# ultrasonic.net
KiCad netlist of a schematic drawn in Altium Designer
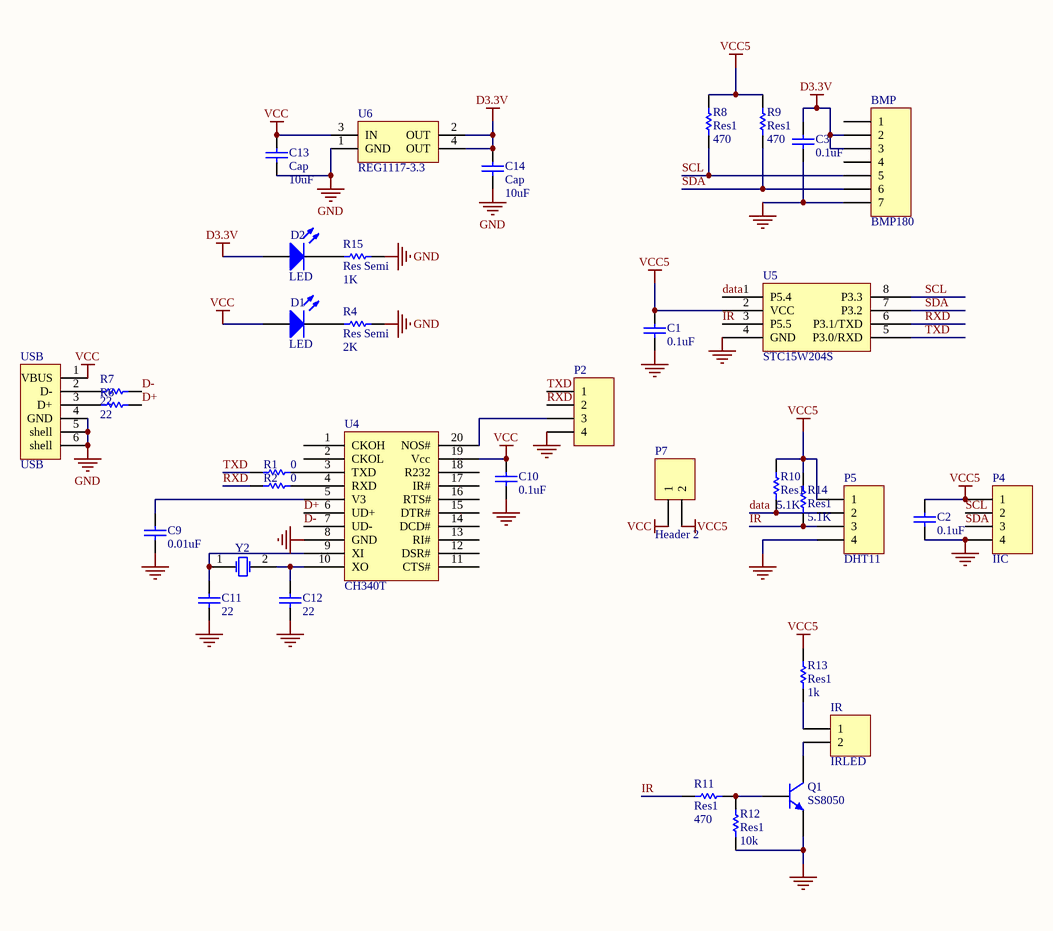
[diagram p0: ultrasonic.SCHDOC]

(export (version "E")
  (design (tool "Eeschema 10.0.6"))
  (components
    (comp (ref "BMP")
      (value "BMP180")
      (footprint "BMP180")
      (description "Header, 7-Pin")
      (fields (field (name "PUBLISHER") "Altium Limited"))
      (libsource (lib "Miscellaneous Connectors") (part "Header 7"))
    )
    (comp (ref "C1")
      (value "0.1uF")
      (footprint "C0603")
      (description "Capacitor")
      (fields (field (name "Comment") "Cap") (field (name "PUBLISHER") "Altium Limited"))
      (libsource (lib "Miscellaneous Devices") (part "Cap"))
    )
    (comp (ref "C2")
      (value "0.1uF")
      (footprint "C0603")
      (description "Capacitor")
      (fields (field (name "Comment") "Cap") (field (name "PUBLISHER") "Altium Limited"))
      (libsource (lib "Miscellaneous Devices") (part "Cap"))
    )
    (comp (ref "C3")
      (value "0.1uF")
      (footprint "C0603")
      (description "Capacitor")
      (fields (field (name "Comment") "Cap") (field (name "PUBLISHER") "Altium Limited"))
      (libsource (lib "Miscellaneous Devices") (part "Cap"))
    )
    (comp (ref "C9")
      (value "0.01uF")
      (footprint "C0603")
      (description "Capacitor")
      (fields (field (name "Comment") "Cap") (field (name "PUBLISHER") "Altium Limited"))
      (libsource (lib "Miscellaneous Devices") (part "Cap"))
    )
    (comp (ref "C10")
      (value "0.1uF")
      (footprint "C0603")
      (description "Capacitor")
      (fields (field (name "Comment") "Cap") (field (name "PUBLISHER") "Altium Limited"))
      (libsource (lib "Miscellaneous Devices") (part "Cap"))
    )
    (comp (ref "C11")
      (value "22")
      (footprint "C0603")
      (description "Capacitor")
      (fields (field (name "Comment") "Cap") (field (name "PUBLISHER") "Altium Limited"))
      (libsource (lib "Miscellaneous Devices") (part "Cap"))
    )
    (comp (ref "C12")
      (value "22")
      (footprint "C0603")
      (description "Capacitor")
      (fields (field (name "Comment") "Cap") (field (name "PUBLISHER") "Altium Limited"))
      (libsource (lib "Miscellaneous Devices") (part "Cap"))
    )
    (comp (ref "C13")
      (value "Cap")
      (footprint "CAP0805(2512)")
      (description "Capacitor")
      (fields (field (name "ALTIUM_VALUE") "10uF") (field (name "PUBLISHER") "Altium Limited"))
      (libsource (lib "Miscellaneous Devices") (part "Cap"))
    )
    (comp (ref "C14")
      (value "Cap")
      (footprint "RES0805(2012M)")
      (description "Capacitor")
      (fields (field (name "ALTIUM_VALUE") "10uF") (field (name "PUBLISHER") "Altium Limited"))
      (libsource (lib "Miscellaneous Devices") (part "Cap"))
    )
    (comp (ref "D1")
      (value "LED")
      (footprint "LED_0805")
      (description "Typical BLUE SiC LED")
      (fields (field (name "PUBLISHER") "Altium Limited"))
      (libsource (lib "Miscellaneous Devices") (part "LED3"))
    )
    (comp (ref "D2")
      (value "LED")
      (footprint "LED_0805")
      (description "Typical BLUE SiC LED")
      (fields (field (name "PUBLISHER") "Altium Limited"))
      (libsource (lib "Miscellaneous Devices") (part "LED3"))
    )
    (comp (ref "IR")
      (value "IRLED")
      (footprint "HDR1X2")
      (description "Header, 2-Pin")
      (fields (field (name "PUBLISHER") "Altium Limited"))
      (libsource (lib "") (part "Header 2_1"))
    )
    (comp (ref "P2")
      (value "Header 4")
      (footprint "HDR1X4")
      (description "Header, 4-Pin")
      (fields (field (name "PUBLISHER") "Altium Limited"))
      (libsource (lib "Miscellaneous Connectors") (part "Header 4"))
    )
    (comp (ref "P4")
      (value "IIC")
      (footprint "HDR1X4")
      (description "Header, 4-Pin")
      (fields (field (name "PUBLISHER") "Altium Limited"))
      (libsource (lib "Miscellaneous Connectors") (part "Header 4"))
    )
    (comp (ref "P5")
      (value "DHT11")
      (footprint "HDR1X4")
      (description "Header, 4-Pin")
      (fields (field (name "PUBLISHER") "Altium Limited"))
      (libsource (lib "Miscellaneous Connectors") (part "Header 4"))
    )
    (comp (ref "P7")
      (value "Header 2")
      (footprint "HDR1X2")
      (description "Header, 2-Pin")
      (fields (field (name "PUBLISHER") "Altium Limited"))
      (libsource (lib "Miscellaneous Connectors") (part "Header 2"))
    )
    (comp (ref "Q1")
      (value "SS8050")
      (footprint "SOT95P240-3N")
      (description "NPN Bipolar Transistor")
      (fields (field (name "PUBLISHER") "Altium Limited"))
      (libsource (lib "Miscellaneous Devices") (part "NPN"))
    )
    (comp (ref "R1")
      (value "0")
      (footprint "C0603")
      (description "Semiconductor Resistor")
      (fields (field (name "Comment") "Res Semi") (field (name "PUBLISHER") "Altium Limited"))
      (libsource (lib "Miscellaneous Devices") (part "Res Semi"))
    )
    (comp (ref "R2")
      (value "0")
      (footprint "C0603")
      (description "Semiconductor Resistor")
      (fields (field (name "Comment") "Res Semi") (field (name "PUBLISHER") "Altium Limited"))
      (libsource (lib "Miscellaneous Devices") (part "Res Semi"))
    )
    (comp (ref "R4")
      (value "Res Semi")
      (footprint "C0603")
      (description "Semiconductor Resistor")
      (fields (field (name "ALTIUM_VALUE") "2K") (field (name "PUBLISHER") "Altium Limited"))
      (libsource (lib "Miscellaneous Devices") (part "Res Semi"))
    )
    (comp (ref "R6")
      (value "22")
      (footprint "C0603")
      (description "Semiconductor Resistor")
      (fields (field (name "Comment") "Res Semi") (field (name "PUBLISHER") "Altium Limited"))
      (libsource (lib "Miscellaneous Devices") (part "Res Semi"))
    )
    (comp (ref "R7")
      (value "22")
      (footprint "C0603")
      (description "Semiconductor Resistor")
      (fields (field (name "Comment") "Res Semi") (field (name "PUBLISHER") "Altium Limited"))
      (libsource (lib "Miscellaneous Devices") (part "Res Semi"))
    )
    (comp (ref "R8")
      (value "Res1")
      (footprint "C0603")
      (description "Resistor")
      (fields (field (name "ALTIUM_VALUE") "470") (field (name "PUBLISHER") "Altium Limited"))
      (libsource (lib "Miscellaneous Devices") (part "Res1"))
    )
    (comp (ref "R9")
      (value "Res1")
      (footprint "C0603")
      (description "Resistor")
      (fields (field (name "ALTIUM_VALUE") "470") (field (name "PUBLISHER") "Altium Limited"))
      (libsource (lib "Miscellaneous Devices") (part "Res1"))
    )
    (comp (ref "R10")
      (value "Res1")
      (footprint "C0603")
      (description "Resistor")
      (fields (field (name "ALTIUM_VALUE") "5.1K") (field (name "PUBLISHER") "Altium Limited"))
      (libsource (lib "Miscellaneous Devices") (part "Res1"))
    )
    (comp (ref "R11")
      (value "Res1")
      (footprint "C0603")
      (description "Resistor")
      (fields (field (name "ALTIUM_VALUE") "470") (field (name "PUBLISHER") "Altium Limited"))
      (libsource (lib "Miscellaneous Devices") (part "Res1"))
    )
    (comp (ref "R12")
      (value "Res1")
      (footprint "C0603")
      (description "Resistor")
      (fields (field (name "ALTIUM_VALUE") "10k") (field (name "PUBLISHER") "Altium Limited"))
      (libsource (lib "Miscellaneous Devices") (part "Res1"))
    )
    (comp (ref "R13")
      (value "Res1")
      (footprint "RES0805(2012M)")
      (description "Resistor")
      (fields (field (name "ALTIUM_VALUE") "1k") (field (name "PUBLISHER") "Altium Limited"))
      (libsource (lib "Miscellaneous Devices") (part "Res1"))
    )
    (comp (ref "R14")
      (value "Res1")
      (footprint "C0603")
      (description "Resistor")
      (fields (field (name "ALTIUM_VALUE") "5.1K") (field (name "PUBLISHER") "Altium Limited"))
      (libsource (lib "Miscellaneous Devices") (part "Res1"))
    )
    (comp (ref "R15")
      (value "Res Semi")
      (footprint "C0603")
      (description "Semiconductor Resistor")
      (fields (field (name "ALTIUM_VALUE") "1K") (field (name "PUBLISHER") "Altium Limited"))
      (libsource (lib "Miscellaneous Devices") (part "Res Semi"))
    )
    (comp (ref "U4") (value "CH340T") (footprint "SOP20") (libsource (lib "my") (part "CH340")))
    (comp (ref "U5") (value "STC15W204S") (footprint "SOP8") (libsource (lib "stc") (part "stc15f204s_sop8")))
    (comp (ref "U6")
      (value "REG1117-3.3")
      (footprint "ZZ311")
      (description "800mA and 1A Low Dropout Positive Regulator 2.85V, 3.3V, 5V, and Adjustable")
      (fields (field (name "PUBLISHER") "Altium Limited"))
      (libsource (lib "power") (part "REG1117-3.3"))
    )
    (comp (ref "USB") (value "USB") (footprint "USB-JSZ") (libsource (lib "*") (part "USB")))
    (comp (ref "Y2")
      (value "XTAL")
      (footprint "XTAL-5032")
      (description "Crystal Oscillator")
      (fields (field (name "PUBLISHER") "Altium Limited"))
      (libsource (lib "Miscellaneous Devices") (part "XTAL"))
    )
  )
  (nets
    (net (code "1") (name "/D+") (class "Default")
      (node (ref "R6") (pin "2") (pinfunction "2_2") (pintype "passive"))
      (node (ref "U4") (pin "6") (pinfunction "UD+_6") (pintype "passive"))
    )
    (net (code "2") (name "/D-") (class "Default")
      (node (ref "R7") (pin "2") (pinfunction "2_2") (pintype "passive"))
      (node (ref "U4") (pin "7") (pinfunction "UD-_7") (pintype "passive"))
    )
    (net (code "3") (name "/IR") (class "Default")
      (node (ref "P5") (pin "3") (pinfunction "3_3") (pintype "passive"))
      (node (ref "R11") (pin "2") (pinfunction "2_2") (pintype "passive"))
      (node (ref "R14") (pin "1") (pinfunction "1_1") (pintype "passive"))
      (node (ref "U5") (pin "3") (pinfunction "P5.5_3") (pintype "passive"))
    )
    (net (code "4") (name "/RXD") (class "Default")
      (node (ref "P2") (pin "2") (pinfunction "2_2") (pintype "passive"))
      (node (ref "R2") (pin "1") (pinfunction "1_1") (pintype "passive"))
      (node (ref "U5") (pin "6") (pinfunction "P3.1/TXD_6") (pintype "passive"))
    )
    (net (code "5") (name "/SCL") (class "Default")
      (node (ref "BMP") (pin "5") (pinfunction "5_5") (pintype "passive"))
      (node (ref "P4") (pin "2") (pinfunction "2_2") (pintype "passive"))
      (node (ref "R8") (pin "1") (pinfunction "1_1") (pintype "passive"))
      (node (ref "U5") (pin "8") (pinfunction "P3.3_8") (pintype "passive"))
    )
    (net (code "6") (name "/SDA") (class "Default")
      (node (ref "BMP") (pin "6") (pinfunction "6_6") (pintype "passive"))
      (node (ref "P4") (pin "3") (pinfunction "3_3") (pintype "passive"))
      (node (ref "R9") (pin "1") (pinfunction "1_1") (pintype "passive"))
      (node (ref "U5") (pin "7") (pinfunction "P3.2_7") (pintype "passive"))
    )
    (net (code "7") (name "/TXD") (class "Default")
      (node (ref "P2") (pin "1") (pinfunction "1_1") (pintype "passive"))
      (node (ref "R1") (pin "1") (pinfunction "1_1") (pintype "passive"))
      (node (ref "U5") (pin "5") (pinfunction "P3.0/RXD_5") (pintype "passive"))
    )
    (net (code "8") (name "/data") (class "Default")
      (node (ref "P5") (pin "2") (pinfunction "2_2") (pintype "passive"))
      (node (ref "R10") (pin "1") (pinfunction "1_1") (pintype "passive"))
      (node (ref "U5") (pin "1") (pinfunction "P5.4_1") (pintype "passive"))
    )
    (net (code "9") (name "D3.3V") (class "Default")
      (node (ref "BMP") (pin "2") (pinfunction "2_2") (pintype "passive"))
      (node (ref "BMP") (pin "3") (pinfunction "3_3") (pintype "passive"))
      (node (ref "C14") (pin "1") (pinfunction "1_1") (pintype "passive"))
      (node (ref "C3") (pin "2") (pinfunction "2_2") (pintype "passive"))
      (node (ref "D2") (pin "1") (pinfunction "A_1") (pintype "passive"))
      (node (ref "U6") (pin "2") (pinfunction "OUT_2") (pintype "power_in"))
      (node (ref "U6") (pin "4") (pinfunction "OUT_4") (pintype "power_in"))
    )
    (net (code "10") (name "GND") (class "Default")
      (node (ref "BMP") (pin "7") (pinfunction "7_7") (pintype "passive"))
      (node (ref "C1") (pin "1") (pinfunction "1_1") (pintype "passive"))
      (node (ref "C10") (pin "1") (pinfunction "1_1") (pintype "passive"))
      (node (ref "C11") (pin "1") (pinfunction "1_1") (pintype "passive"))
      (node (ref "C12") (pin "1") (pinfunction "1_1") (pintype "passive"))
      (node (ref "C13") (pin "2") (pinfunction "2_2") (pintype "passive"))
      (node (ref "C14") (pin "2") (pinfunction "2_2") (pintype "passive"))
      (node (ref "C2") (pin "1") (pinfunction "1_1") (pintype "passive"))
      (node (ref "C3") (pin "1") (pinfunction "1_1") (pintype "passive"))
      (node (ref "C9") (pin "1") (pinfunction "1_1") (pintype "passive"))
      (node (ref "P2") (pin "4") (pinfunction "4_4") (pintype "passive"))
      (node (ref "P4") (pin "4") (pinfunction "4_4") (pintype "passive"))
      (node (ref "P5") (pin "4") (pinfunction "4_4") (pintype "passive"))
      (node (ref "Q1") (pin "3") (pinfunction "E_3") (pintype "passive"))
      (node (ref "R12") (pin "2") (pinfunction "2_2") (pintype "passive"))
      (node (ref "R15") (pin "1") (pinfunction "1_1") (pintype "passive"))
      (node (ref "R4") (pin "1") (pinfunction "1_1") (pintype "passive"))
      (node (ref "U4") (pin "8") (pinfunction "GND_8") (pintype "passive"))
      (node (ref "U5") (pin "4") (pinfunction "GND_4") (pintype "passive"))
      (node (ref "U6") (pin "1") (pinfunction "GND_1") (pintype "power_in"))
      (node (ref "USB") (pin "4") (pinfunction "GND_4") (pintype "passive"))
      (node (ref "USB") (pin "5") (pinfunction "shell_5") (pintype "passive"))
      (node (ref "USB") (pin "6") (pinfunction "shell_6") (pintype "passive"))
    )
    (net (code "11") (name "Net-(D1-K)") (class "Default")
      (node (ref "D1") (pin "2") (pinfunction "K_2") (pintype "passive"))
      (node (ref "R4") (pin "2") (pinfunction "2_2") (pintype "passive"))
    )
    (net (code "12") (name "Net-(D2-K)") (class "Default")
      (node (ref "D2") (pin "2") (pinfunction "K_2") (pintype "passive"))
      (node (ref "R15") (pin "2") (pinfunction "2_2") (pintype "passive"))
    )
    (net (code "13") (name "Net-(IR-Pad1)") (class "Default")
      (node (ref "IR") (pin "1") (pinfunction "1_1") (pintype "passive"))
      (node (ref "R13") (pin "2") (pinfunction "2_2") (pintype "passive"))
    )
    (net (code "14") (name "Net-(Q1-B)") (class "Default")
      (node (ref "Q1") (pin "2") (pinfunction "B_2") (pintype "passive"))
      (node (ref "R11") (pin "1") (pinfunction "1_1") (pintype "passive"))
      (node (ref "R12") (pin "1") (pinfunction "1_1") (pintype "passive"))
    )
    (net (code "15") (name "Net-(Q1-C)") (class "Default")
      (node (ref "IR") (pin "2") (pinfunction "2_2") (pintype "passive"))
      (node (ref "Q1") (pin "1") (pinfunction "C_1") (pintype "passive"))
    )
    (net (code "16") (name "Net-(U4-NOS#)") (class "Default")
      (node (ref "P2") (pin "3") (pinfunction "3_3") (pintype "passive"))
      (node (ref "U4") (pin "20") (pinfunction "NOS#_20") (pintype "passive"))
    )
    (net (code "17") (name "Net-(U4-RXD)") (class "Default")
      (node (ref "R2") (pin "2") (pinfunction "2_2") (pintype "passive"))
      (node (ref "U4") (pin "4") (pinfunction "RXD_4") (pintype "passive"))
    )
    (net (code "18") (name "Net-(U4-TXD)") (class "Default")
      (node (ref "R1") (pin "2") (pinfunction "2_2") (pintype "passive"))
      (node (ref "U4") (pin "3") (pinfunction "TXD_3") (pintype "passive"))
    )
    (net (code "19") (name "Net-(U4-V3)") (class "Default")
      (node (ref "C9") (pin "2") (pinfunction "2_2") (pintype "passive"))
      (node (ref "U4") (pin "5") (pinfunction "V3_5") (pintype "passive"))
    )
    (net (code "20") (name "Net-(U4-XI)") (class "Default")
      (node (ref "C11") (pin "2") (pinfunction "2_2") (pintype "passive"))
      (node (ref "U4") (pin "9") (pinfunction "XI_9") (pintype "passive"))
      (node (ref "Y2") (pin "1") (pinfunction "OSC1_1") (pintype "passive"))
    )
    (net (code "21") (name "Net-(U4-XO)") (class "Default")
      (node (ref "C12") (pin "2") (pinfunction "2_2") (pintype "passive"))
      (node (ref "U4") (pin "10") (pinfunction "XO_10") (pintype "passive"))
      (node (ref "Y2") (pin "2") (pinfunction "OSC2_2") (pintype "passive"))
    )
    (net (code "22") (name "Net-(USB-D+)") (class "Default")
      (node (ref "R6") (pin "1") (pinfunction "1_1") (pintype "passive"))
      (node (ref "USB") (pin "3") (pinfunction "D+_3") (pintype "passive"))
    )
    (net (code "23") (name "Net-(USB-D-)") (class "Default")
      (node (ref "R7") (pin "1") (pinfunction "1_1") (pintype "passive"))
      (node (ref "USB") (pin "2") (pinfunction "D-_2") (pintype "passive"))
    )
    (net (code "24") (name "VCC") (class "Default")
      (node (ref "C10") (pin "2") (pinfunction "2_2") (pintype "passive"))
      (node (ref "C13") (pin "1") (pinfunction "1_1") (pintype "passive"))
      (node (ref "D1") (pin "1") (pinfunction "A_1") (pintype "passive"))
      (node (ref "P7") (pin "1") (pinfunction "1_1") (pintype "passive"))
      (node (ref "U4") (pin "19") (pinfunction "Vcc_19") (pintype "passive"))
      (node (ref "U6") (pin "3") (pinfunction "IN_3") (pintype "power_in"))
      (node (ref "USB") (pin "1") (pinfunction "VBUS_1") (pintype "passive"))
    )
    (net (code "25") (name "VCC5") (class "Default")
      (node (ref "C1") (pin "2") (pinfunction "2_2") (pintype "passive"))
      (node (ref "C2") (pin "2") (pinfunction "2_2") (pintype "passive"))
      (node (ref "P4") (pin "1") (pinfunction "1_1") (pintype "passive"))
      (node (ref "P5") (pin "1") (pinfunction "1_1") (pintype "passive"))
      (node (ref "P7") (pin "2") (pinfunction "2_2") (pintype "passive"))
      (node (ref "R10") (pin "2") (pinfunction "2_2") (pintype "passive"))
      (node (ref "R13") (pin "1") (pinfunction "1_1") (pintype "passive"))
      (node (ref "R14") (pin "2") (pinfunction "2_2") (pintype "passive"))
      (node (ref "R8") (pin "2") (pinfunction "2_2") (pintype "passive"))
      (node (ref "R9") (pin "2") (pinfunction "2_2") (pintype "passive"))
      (node (ref "U5") (pin "2") (pinfunction "VCC_2") (pintype "passive"))
    )
    (net (code "26") (name "unconnected-(BMP-Pad1)") (class "Default")
      (node (ref "BMP") (pin "1") (pinfunction "1_1") (pintype "passive"))
    )
    (net (code "27") (name "unconnected-(BMP-Pad4)") (class "Default")
      (node (ref "BMP") (pin "4") (pinfunction "4_4") (pintype "passive"))
    )
    (net (code "28") (name "unconnected-(U4-CKOH-Pad1)") (class "Default")
      (node (ref "U4") (pin "1") (pinfunction "CKOH_1") (pintype "passive"))
    )
    (net (code "29") (name "unconnected-(U4-CKOL-Pad2)") (class "Default")
      (node (ref "U4") (pin "2") (pinfunction "CKOL_2") (pintype "passive"))
    )
    (net (code "30") (name "unconnected-(U4-CTS#-Pad11)") (class "Default")
      (node (ref "U4") (pin "11") (pinfunction "CTS#_11") (pintype "passive"))
    )
    (net (code "31") (name "unconnected-(U4-DCD#-Pad14)") (class "Default")
      (node (ref "U4") (pin "14") (pinfunction "DCD#_14") (pintype "passive"))
    )
    (net (code "32") (name "unconnected-(U4-DSR#-Pad12)") (class "Default")
      (node (ref "U4") (pin "12") (pinfunction "DSR#_12") (pintype "passive"))
    )
    (net (code "33") (name "unconnected-(U4-DTR#-Pad15)") (class "Default")
      (node (ref "U4") (pin "15") (pinfunction "DTR#_15") (pintype "passive"))
    )
    (net (code "34") (name "unconnected-(U4-IR#-Pad17)") (class "Default")
      (node (ref "U4") (pin "17") (pinfunction "IR#_17") (pintype "passive"))
    )
    (net (code "35") (name "unconnected-(U4-R232-Pad18)") (class "Default")
      (node (ref "U4") (pin "18") (pinfunction "R232_18") (pintype "passive"))
    )
    (net (code "36") (name "unconnected-(U4-RI#-Pad13)") (class "Default")
      (node (ref "U4") (pin "13") (pinfunction "RI#_13") (pintype "passive"))
    )
    (net (code "37") (name "unconnected-(U4-RTS#-Pad16)") (class "Default")
      (node (ref "U4") (pin "16") (pinfunction "RTS#_16") (pintype "passive"))
    )
  )
)
